# SOM_BOOT.net
KiCad netlist of a schematic drawn in Altium Designer
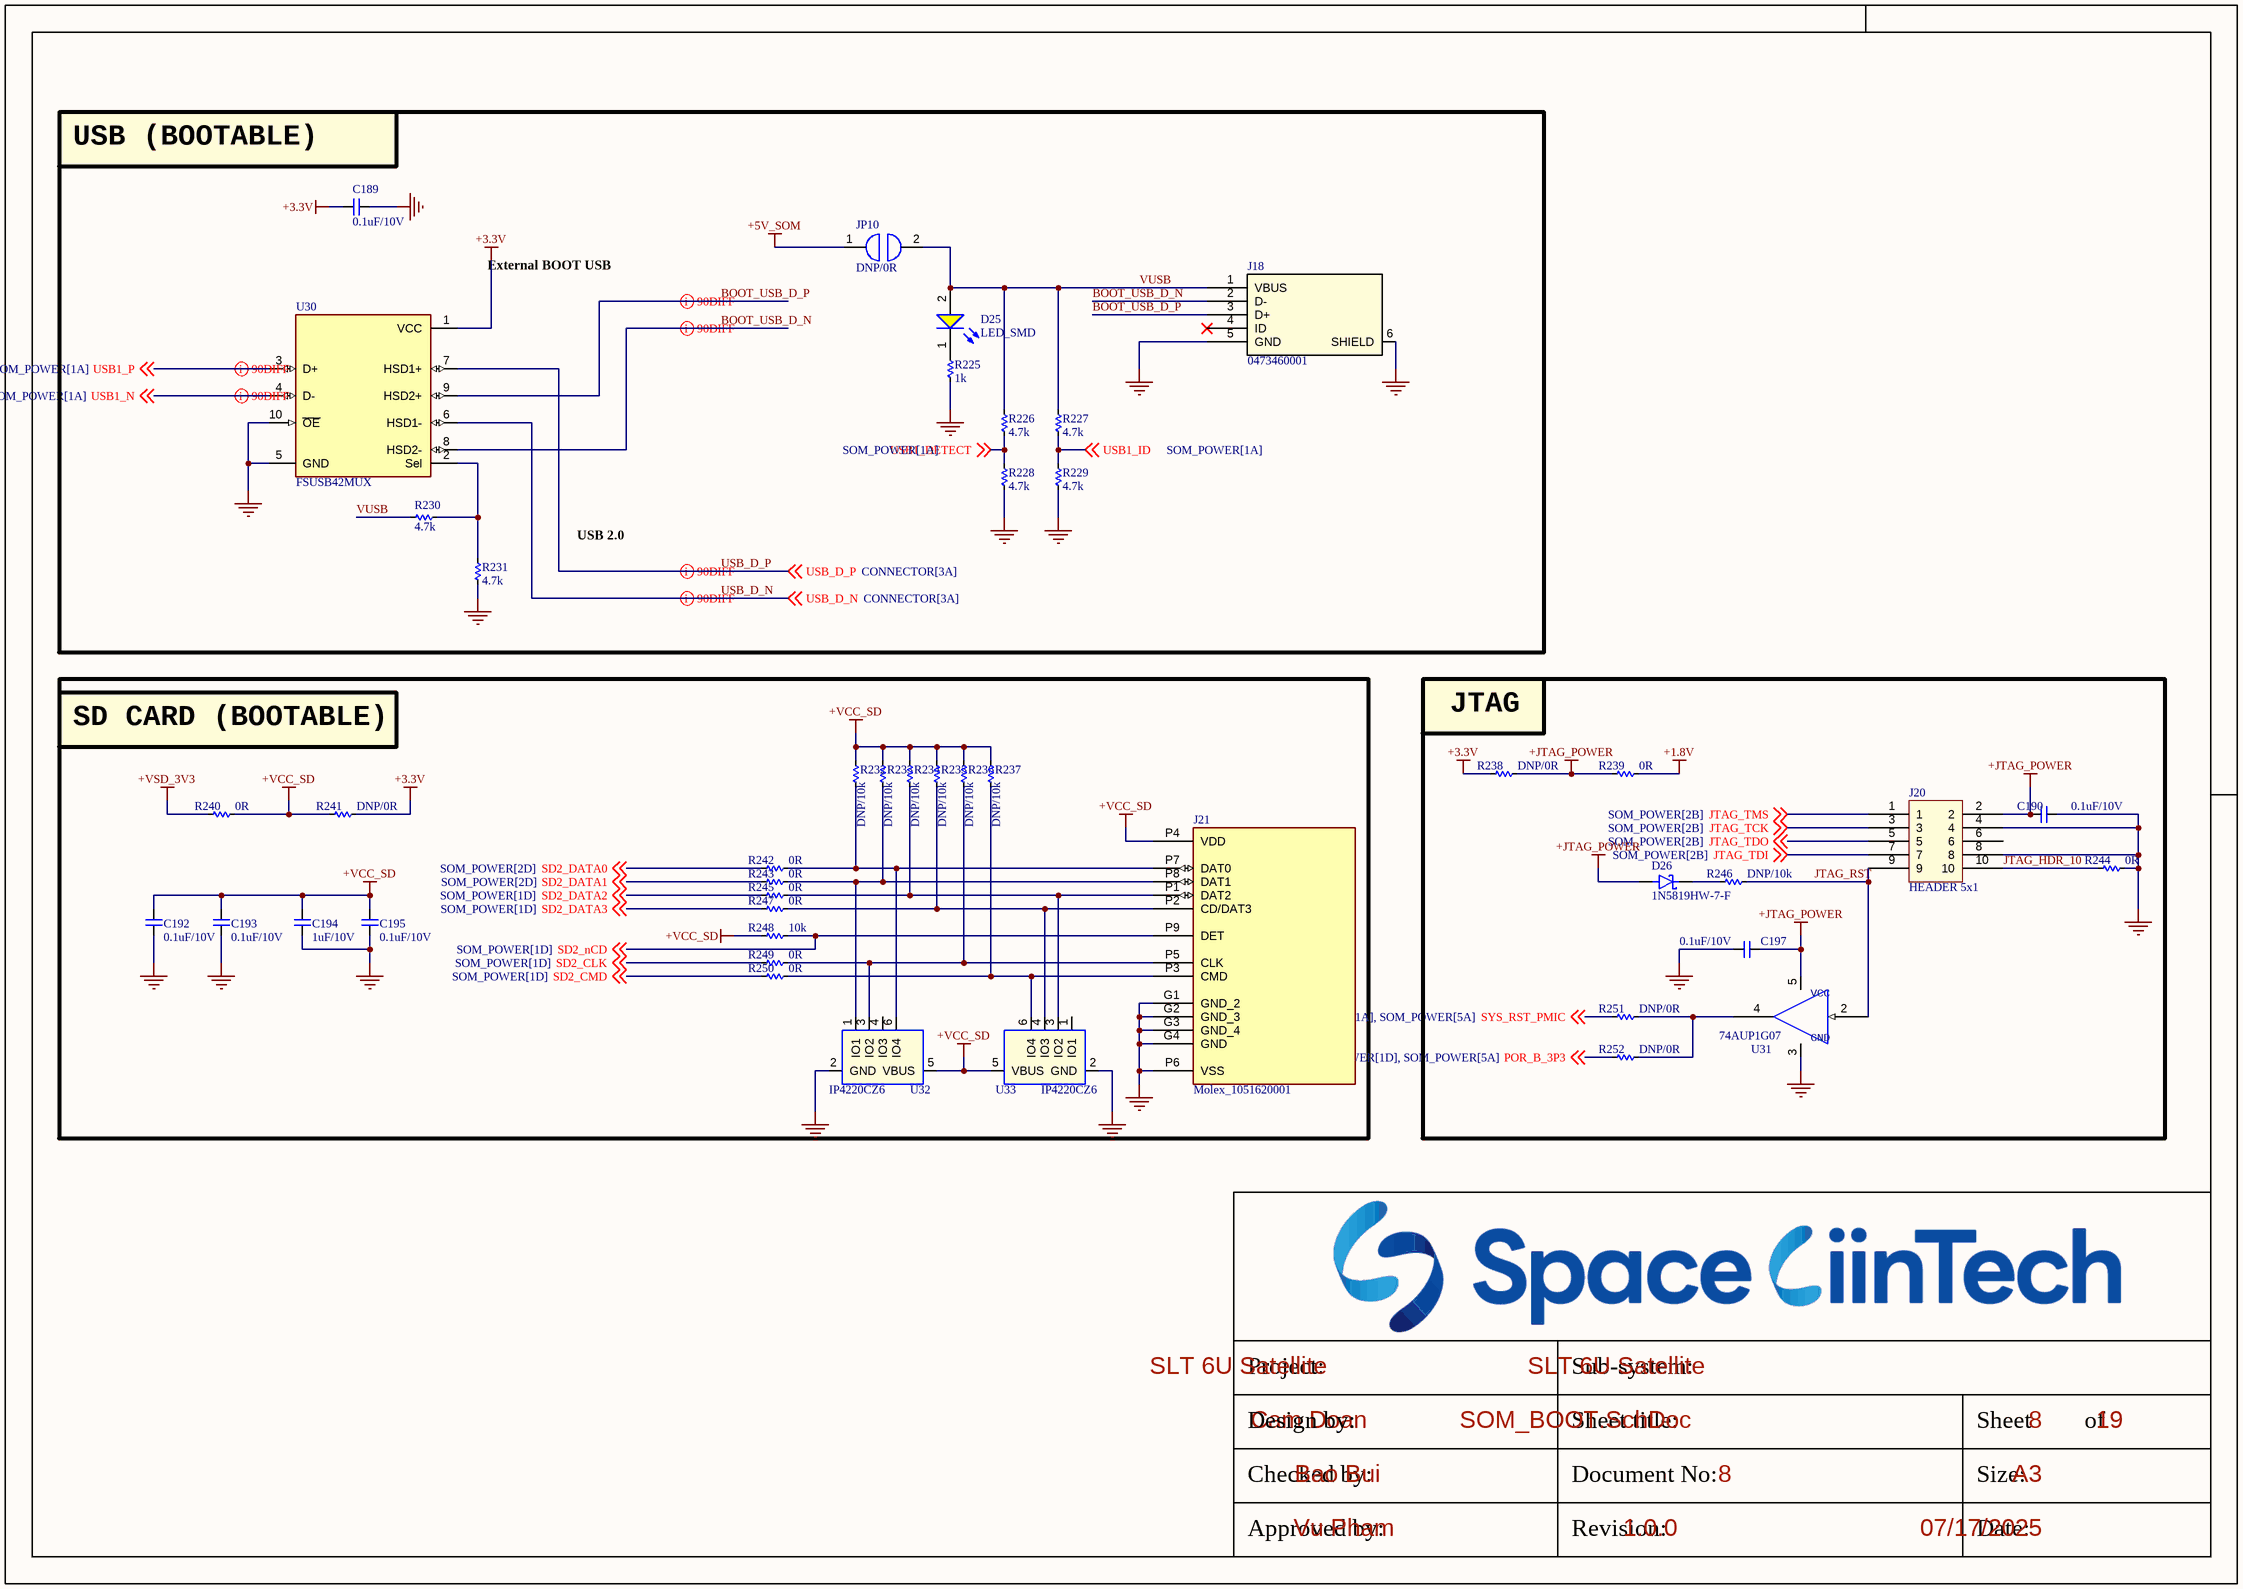
[diagram p0: SOM_BOOT.SchDoc]

(export (version "E")
  (design (tool "Eeschema 10.0.6"))
  (components
    (comp (ref "C189")
      (value "0.1uF/10V")
      (footprint "CAP_C_1005X60")
      (description "CAP CHIP")
      (libsource (lib "LABLIB") (part "_CAP_C_2"))
    )
    (comp (ref "C190")
      (value "0.1uF/10V")
      (footprint "CAP_C_1005X60")
      (description "CAP CHIP")
      (libsource (lib "LABLIB") (part "_CAP_C_2"))
    )
    (comp (ref "C192")
      (value "0.1uF/10V")
      (footprint "CAP_C_1005X60")
      (description "CAP CHIP")
      (libsource (lib "LABLIB") (part "_CAP_C_2"))
    )
    (comp (ref "C193")
      (value "0.1uF/10V")
      (footprint "CAP_C_1005X60")
      (description "CAP CHIP")
      (libsource (lib "LABLIB") (part "_CAP_C_2"))
    )
    (comp (ref "C194")
      (value "1uF/10V")
      (footprint "CAP_C_1005X60")
      (description "CAP CHIP")
      (libsource (lib "LABLIB") (part "_CAP_C_2"))
    )
    (comp (ref "C195")
      (value "0.1uF/10V")
      (footprint "CAP_C_1005X60")
      (description "CAP CHIP")
      (libsource (lib "LABLIB") (part "_CAP_C_2"))
    )
    (comp (ref "C197")
      (value "0.1uF/10V")
      (footprint "CAP_C_1005X60")
      (description "CAP CHIP")
      (libsource (lib "LABLIB") (part "_CAP_C_2"))
    )
    (comp (ref "D25") (value "LED_SMD") (footprint "LED_0603") (libsource (lib "LABLIB") (part "LED_SMD")))
    (comp (ref "D26")
      (value "1N5819HW-7-F")
      (footprint "SOD3717X145N")
      (description "DIODE SCHOTTKY 40V 1A SOD123")
      (libsource (lib "LABLIB") (part "DIODE SCHOTTKY"))
    )
    (comp (ref "J18")
      (value "0473460001")
      (footprint "47346-0001_MOL")
      (description "No Description Available")
      (libsource (lib "obc_ver2") (part "USB_micro"))
    )
    (comp (ref "J20")
      (value "HEADER 5x1")
      (footprint "CONN_54202-T0805ALF")
      (libsource (lib "LABLIB") (part "Header 5x2_Z"))
    )
    (comp (ref "J21")
      (value "Molex_1051620001")
      (footprint "Molex_1051620001")
      (description "9 (8 + 1) Position Card Connector Secure Digital - microSDâ„¢ Surface Mount, Right Angle Gold")
      (fields (field (name "MF") "Molex") (field (name "MP") "1051620001"))
      (libsource (lib "new_component") (part "Molex_1051620001"))
    )
    (comp (ref "JP10")
      (value "DNP/0R")
      (footprint "RES_C_1608X60")
      (libsource (lib "EXP_V1") (part "JUMPER"))
    )
    (comp (ref "R225")
      (value "1k")
      (footprint "RES_C_1005X40")
      (description "RES")
      (libsource (lib "LABLIB") (part "_RES_B_2"))
    )
    (comp (ref "R226")
      (value "4.7k")
      (footprint "RES_C_1005X40")
      (description "RES")
      (libsource (lib "LABLIB") (part "_RES_B_2"))
    )
    (comp (ref "R227")
      (value "4.7k")
      (footprint "RES_C_1005X40")
      (description "RES")
      (libsource (lib "LABLIB") (part "_RES_B_2"))
    )
    (comp (ref "R228")
      (value "4.7k")
      (footprint "RES_C_1005X40")
      (description "RES")
      (libsource (lib "LABLIB") (part "_RES_B_2"))
    )
    (comp (ref "R229")
      (value "4.7k")
      (footprint "RES_C_1005X40")
      (description "RES")
      (libsource (lib "LABLIB") (part "_RES_B_2"))
    )
    (comp (ref "R230")
      (value "4.7k")
      (footprint "RES_C_1005X40")
      (description "RES")
      (libsource (lib "LABLIB") (part "_RES_B_2"))
    )
    (comp (ref "R231")
      (value "4.7k")
      (footprint "RES_C_1005X40")
      (description "RES")
      (libsource (lib "LABLIB") (part "_RES_B_2"))
    )
    (comp (ref "R232")
      (value "DNP/10k")
      (footprint "RES_C_1005X40")
      (description "RES")
      (libsource (lib "LABLIB") (part "_RES_B_2"))
    )
    (comp (ref "R233")
      (value "DNP/10k")
      (footprint "RES_C_1005X40")
      (description "RES")
      (libsource (lib "LABLIB") (part "_RES_B_2"))
    )
    (comp (ref "R234")
      (value "DNP/10k")
      (footprint "RES_C_1005X40")
      (description "RES")
      (libsource (lib "LABLIB") (part "_RES_B_2"))
    )
    (comp (ref "R235")
      (value "DNP/10k")
      (footprint "RES_C_1005X40")
      (description "RES")
      (libsource (lib "LABLIB") (part "_RES_B_2"))
    )
    (comp (ref "R236")
      (value "DNP/10k")
      (footprint "RES_C_1005X40")
      (description "RES")
      (libsource (lib "LABLIB") (part "_RES_B_2"))
    )
    (comp (ref "R237")
      (value "DNP/10k")
      (footprint "RES_C_1005X40")
      (description "RES")
      (libsource (lib "LABLIB") (part "_RES_B_2"))
    )
    (comp (ref "R238")
      (value "DNP/0R")
      (footprint "RES_C_1005X40")
      (description "RES")
      (libsource (lib "LABLIB") (part "_RES_B_2"))
    )
    (comp (ref "R239")
      (value "0R")
      (footprint "RES_C_1005X40")
      (description "RES")
      (libsource (lib "LABLIB") (part "_RES_B_2"))
    )
    (comp (ref "R240")
      (value "0R")
      (footprint "RES_C_1005X40")
      (description "RES")
      (libsource (lib "LABLIB") (part "_RES_B_2"))
    )
    (comp (ref "R241")
      (value "DNP/0R")
      (footprint "RES_C_1005X40")
      (description "RES")
      (libsource (lib "LABLIB") (part "_RES_B_2"))
    )
    (comp (ref "R242")
      (value "0R")
      (footprint "RES_C_1005X40")
      (description "RES")
      (libsource (lib "LABLIB") (part "_RES_B_2"))
    )
    (comp (ref "R243")
      (value "0R")
      (footprint "RES_C_1005X40")
      (description "RES")
      (libsource (lib "LABLIB") (part "_RES_B_2"))
    )
    (comp (ref "R244")
      (value "0R")
      (footprint "RES_C_1005X40")
      (description "RES")
      (libsource (lib "LABLIB") (part "_RES_B_2"))
    )
    (comp (ref "R245")
      (value "0R")
      (footprint "RES_C_1005X40")
      (description "RES")
      (libsource (lib "LABLIB") (part "_RES_B_2"))
    )
    (comp (ref "R246")
      (value "DNP/10k")
      (footprint "RES_C_1005X40")
      (description "RES")
      (libsource (lib "LABLIB") (part "_RES_B_2"))
    )
    (comp (ref "R247")
      (value "0R")
      (footprint "RES_C_1005X40")
      (description "RES")
      (libsource (lib "LABLIB") (part "_RES_B_2"))
    )
    (comp (ref "R248")
      (value "10k")
      (footprint "RES_C_1005X40")
      (description "RES")
      (libsource (lib "LABLIB") (part "_RES_B_2"))
    )
    (comp (ref "R249")
      (value "0R")
      (footprint "RES_C_1005X40")
      (description "RES")
      (libsource (lib "LABLIB") (part "_RES_B_2"))
    )
    (comp (ref "R250")
      (value "0R")
      (footprint "RES_C_1005X40")
      (description "RES")
      (libsource (lib "LABLIB") (part "_RES_B_2"))
    )
    (comp (ref "R251")
      (value "DNP/0R")
      (footprint "RES_C_1005X40")
      (description "RES")
      (libsource (lib "LABLIB") (part "_RES_B_2"))
    )
    (comp (ref "R252")
      (value "DNP/0R")
      (footprint "RES_C_1005X40")
      (description "RES")
      (libsource (lib "LABLIB") (part "_RES_B_2"))
    )
    (comp (ref "U30")
      (value "FSUSB42MUX")
      (footprint "FP-846AP-MFG")
      (description "IC USB SWITCH DPDT 10MSOP")
      (fields (field (name "VOLTAGE") "4.3V"))
      (libsource (lib "Altium Content Vault") (part "e0bd5e1b4e0e4edc77f3356c64bf8f9"))
    )
    (comp (ref "U31")
      (value "74AUP1G07")
      (footprint "SOT-23-5_DIO")
      (libsource (lib "*") (part "74AUP1G07 , buffer ,LV"))
    )
    (comp (ref "U32")
      (value "IP4220CZ6")
      (footprint "SOT95P280X145-6N")
      (libsource (lib "*") (part "IP4220CZ6_0"))
    )
    (comp (ref "U33")
      (value "IP4220CZ6")
      (footprint "SOT95P280X145-6N")
      (libsource (lib "") (part "IP4220CZ6_0_1"))
    )
  )
  (nets
    (net (code "1") (name "+1.8V") (class "Default")
      (node (ref "R239") (pin "1") (pinfunction "1_1") (pintype "passive"))
    )
    (net (code "2") (name "+3.3V") (class "Default")
      (node (ref "C189") (pin "2") (pinfunction "2_2") (pintype "passive"))
      (node (ref "R238") (pin "2") (pinfunction "2_2") (pintype "passive"))
      (node (ref "R241") (pin "2") (pinfunction "2_2") (pintype "passive"))
      (node (ref "U30") (pin "1") (pinfunction "VCC_1") (pintype "power_in"))
    )
    (net (code "3") (name "+5V_SOM") (class "Default")
      (node (ref "JP10") (pin "1") (pinfunction "1_1") (pintype "passive"))
    )
    (net (code "4") (name "+JTAG_POWER") (class "Default")
      (node (ref "C190") (pin "2") (pinfunction "2_2") (pintype "passive"))
      (node (ref "C197") (pin "1") (pinfunction "1_1") (pintype "passive"))
      (node (ref "D26") (pin "2") (pinfunction "A_2") (pintype "passive"))
      (node (ref "J20") (pin "2") (pinfunction "2_2") (pintype "passive"))
      (node (ref "R238") (pin "1") (pinfunction "1_1") (pintype "passive"))
      (node (ref "R239") (pin "2") (pinfunction "2_2") (pintype "passive"))
      (node (ref "U31") (pin "5") (pinfunction "VCC_5") (pintype "power_in"))
    )
    (net (code "5") (name "+VCC_SD") (class "Default")
      (node (ref "C192") (pin "2") (pinfunction "2_2") (pintype "passive"))
      (node (ref "C193") (pin "2") (pinfunction "2_2") (pintype "passive"))
      (node (ref "C194") (pin "2") (pinfunction "2_2") (pintype "passive"))
      (node (ref "C195") (pin "2") (pinfunction "2_2") (pintype "passive"))
      (node (ref "J21") (pin "P4") (pinfunction "VDD_P4") (pintype "power_in"))
      (node (ref "R232") (pin "2") (pinfunction "2_2") (pintype "passive"))
      (node (ref "R233") (pin "2") (pinfunction "2_2") (pintype "passive"))
      (node (ref "R234") (pin "2") (pinfunction "2_2") (pintype "passive"))
      (node (ref "R235") (pin "2") (pinfunction "2_2") (pintype "passive"))
      (node (ref "R236") (pin "2") (pinfunction "2_2") (pintype "passive"))
      (node (ref "R237") (pin "2") (pinfunction "2_2") (pintype "passive"))
      (node (ref "R240") (pin "2") (pinfunction "2_2") (pintype "passive"))
      (node (ref "R241") (pin "1") (pinfunction "1_1") (pintype "passive"))
      (node (ref "R248") (pin "1") (pinfunction "1_1") (pintype "passive"))
      (node (ref "U32") (pin "5") (pinfunction "VBUS_5") (pintype "passive"))
      (node (ref "U33") (pin "5") (pinfunction "VBUS_5") (pintype "passive"))
    )
    (net (code "6") (name "+VSD_3V3") (class "Default")
      (node (ref "R240") (pin "1") (pinfunction "1_1") (pintype "passive"))
    )
    (net (code "7") (name "/BOOT_USB_D_N") (class "Default")
      (node (ref "J18") (pin "2") (pinfunction "D-_2") (pintype "passive"))
      (node (ref "U30") (pin "8") (pinfunction "HSD2-_8") (pintype "bidirectional"))
    )
    (net (code "8") (name "/BOOT_USB_D_P") (class "Default")
      (node (ref "J18") (pin "3") (pinfunction "D+_3") (pintype "passive"))
      (node (ref "U30") (pin "9") (pinfunction "HSD2+_9") (pintype "bidirectional"))
    )
    (net (code "9") (name "/JTAG_HDR_10") (class "Default")
      (node (ref "J20") (pin "10") (pinfunction "10_10") (pintype "passive"))
      (node (ref "R244") (pin "2") (pinfunction "2_2") (pintype "passive"))
    )
    (net (code "10") (name "/JTAG_RST") (class "Default")
      (node (ref "J20") (pin "9") (pinfunction "9_9") (pintype "passive"))
      (node (ref "R246") (pin "1") (pinfunction "1_1") (pintype "passive"))
      (node (ref "U31") (pin "2") (pinfunction "IN_2") (pintype "input"))
    )
    (net (code "11") (name "/VUSB") (class "Default")
      (node (ref "D25") (pin "2") (pinfunction "A_2") (pintype "passive"))
      (node (ref "J18") (pin "1") (pinfunction "VBUS_1") (pintype "passive"))
      (node (ref "JP10") (pin "2") (pinfunction "2_2") (pintype "passive"))
      (node (ref "R226") (pin "2") (pinfunction "2_2") (pintype "passive"))
      (node (ref "R227") (pin "2") (pinfunction "2_2") (pintype "passive"))
      (node (ref "R230") (pin "1") (pinfunction "1_1") (pintype "passive"))
    )
    (net (code "12") (name "GND") (class "Default")
      (node (ref "C189") (pin "1") (pinfunction "1_1") (pintype "passive"))
      (node (ref "C190") (pin "1") (pinfunction "1_1") (pintype "passive"))
      (node (ref "C192") (pin "1") (pinfunction "1_1") (pintype "passive"))
      (node (ref "C193") (pin "1") (pinfunction "1_1") (pintype "passive"))
      (node (ref "C194") (pin "1") (pinfunction "1_1") (pintype "passive"))
      (node (ref "C195") (pin "1") (pinfunction "1_1") (pintype "passive"))
      (node (ref "C197") (pin "2") (pinfunction "2_2") (pintype "passive"))
      (node (ref "J18") (pin "5") (pinfunction "GND_5") (pintype "power_in"))
      (node (ref "J18") (pin "6") (pinfunction "SHIELD_6") (pintype "passive"))
      (node (ref "J20") (pin "4") (pinfunction "4_4") (pintype "passive"))
      (node (ref "J20") (pin "8") (pinfunction "8_8") (pintype "passive"))
      (node (ref "J21") (pin "G1") (pinfunction "GND_2_G1") (pintype "passive"))
      (node (ref "J21") (pin "G2") (pinfunction "GND_3_G2") (pintype "passive"))
      (node (ref "J21") (pin "G3") (pinfunction "GND_4_G3") (pintype "passive"))
      (node (ref "J21") (pin "G4") (pinfunction "GND_G4") (pintype "passive"))
      (node (ref "J21") (pin "P6") (pinfunction "VSS_P6") (pintype "passive"))
      (node (ref "R225") (pin "1") (pinfunction "1_1") (pintype "passive"))
      (node (ref "R228") (pin "1") (pinfunction "1_1") (pintype "passive"))
      (node (ref "R229") (pin "1") (pinfunction "1_1") (pintype "passive"))
      (node (ref "R231") (pin "1") (pinfunction "1_1") (pintype "passive"))
      (node (ref "R244") (pin "1") (pinfunction "1_1") (pintype "passive"))
      (node (ref "U30") (pin "10") (pinfunction "~{OE}_10") (pintype "input"))
      (node (ref "U30") (pin "5") (pinfunction "GND_5") (pintype "power_in"))
      (node (ref "U31") (pin "3") (pinfunction "GND_3") (pintype "power_in"))
      (node (ref "U32") (pin "2") (pinfunction "GND_2") (pintype "passive"))
      (node (ref "U33") (pin "2") (pinfunction "GND_2") (pintype "passive"))
    )
    (net (code "13") (name "JTAG_TCK") (class "Default")
      (node (ref "J20") (pin "3") (pinfunction "3_3") (pintype "passive"))
    )
    (net (code "14") (name "JTAG_TDI") (class "Default")
      (node (ref "J20") (pin "7") (pinfunction "7_7") (pintype "passive"))
    )
    (net (code "15") (name "JTAG_TDO") (class "Default")
      (node (ref "J20") (pin "5") (pinfunction "5_5") (pintype "passive"))
    )
    (net (code "16") (name "JTAG_TMS") (class "Default")
      (node (ref "J20") (pin "1") (pinfunction "1_1") (pintype "passive"))
    )
    (net (code "17") (name "Net-(D25-K)") (class "Default")
      (node (ref "D25") (pin "1") (pinfunction "K_1") (pintype "passive"))
      (node (ref "R225") (pin "2") (pinfunction "2_2") (pintype "passive"))
    )
    (net (code "18") (name "Net-(D26-K)") (class "Default")
      (node (ref "D26") (pin "1") (pinfunction "K_1") (pintype "passive"))
      (node (ref "R246") (pin "2") (pinfunction "2_2") (pintype "passive"))
    )
    (net (code "19") (name "Net-(J21-CD{slash}DAT3)") (class "Default")
      (node (ref "J21") (pin "P2") (pinfunction "CD/DAT3_P2") (pintype "passive"))
      (node (ref "R235") (pin "1") (pinfunction "1_1") (pintype "passive"))
      (node (ref "R247") (pin "2") (pinfunction "2_2") (pintype "passive"))
      (node (ref "U33") (pin "4") (pinfunction "IO3_4") (pintype "passive"))
    )
    (net (code "20") (name "Net-(J21-CLK)") (class "Default")
      (node (ref "J21") (pin "P5") (pinfunction "CLK_P5") (pintype "passive"))
      (node (ref "R236") (pin "1") (pinfunction "1_1") (pintype "passive"))
      (node (ref "R249") (pin "2") (pinfunction "2_2") (pintype "passive"))
      (node (ref "U32") (pin "3") (pinfunction "IO2_3") (pintype "passive"))
    )
    (net (code "21") (name "Net-(J21-CMD)") (class "Default")
      (node (ref "J21") (pin "P3") (pinfunction "CMD_P3") (pintype "passive"))
      (node (ref "R237") (pin "1") (pinfunction "1_1") (pintype "passive"))
      (node (ref "R250") (pin "2") (pinfunction "2_2") (pintype "passive"))
      (node (ref "U33") (pin "6") (pinfunction "IO4_6") (pintype "passive"))
    )
    (net (code "22") (name "Net-(J21-DAT0)") (class "Default")
      (node (ref "J21") (pin "P7") (pinfunction "DAT0_P7") (pintype "bidirectional"))
      (node (ref "R232") (pin "1") (pinfunction "1_1") (pintype "passive"))
      (node (ref "R242") (pin "2") (pinfunction "2_2") (pintype "passive"))
      (node (ref "U32") (pin "6") (pinfunction "IO4_6") (pintype "passive"))
    )
    (net (code "23") (name "Net-(J21-DAT1)") (class "Default")
      (node (ref "J21") (pin "P8") (pinfunction "DAT1_P8") (pintype "bidirectional"))
      (node (ref "R233") (pin "1") (pinfunction "1_1") (pintype "passive"))
      (node (ref "R243") (pin "2") (pinfunction "2_2") (pintype "passive"))
      (node (ref "U32") (pin "1") (pinfunction "IO1_1") (pintype "passive"))
    )
    (net (code "24") (name "Net-(J21-DAT2)") (class "Default")
      (node (ref "J21") (pin "P1") (pinfunction "DAT2_P1") (pintype "bidirectional"))
      (node (ref "R234") (pin "1") (pinfunction "1_1") (pintype "passive"))
      (node (ref "R245") (pin "2") (pinfunction "2_2") (pintype "passive"))
      (node (ref "U33") (pin "3") (pinfunction "IO2_3") (pintype "passive"))
    )
    (net (code "25") (name "Net-(U30-Sel)") (class "Default")
      (node (ref "R230") (pin "2") (pinfunction "2_2") (pintype "passive"))
      (node (ref "R231") (pin "2") (pinfunction "2_2") (pintype "passive"))
      (node (ref "U30") (pin "2") (pinfunction "Sel_2") (pintype "passive"))
    )
    (net (code "26") (name "Net-(U31-OUT)") (class "Default")
      (node (ref "R251") (pin "1") (pinfunction "1_1") (pintype "passive"))
      (node (ref "R252") (pin "1") (pinfunction "1_1") (pintype "passive"))
      (node (ref "U31") (pin "4") (pinfunction "OUT_4") (pintype "open_collector"))
    )
    (net (code "27") (name "POR_B_3P3") (class "Default")
      (node (ref "R252") (pin "2") (pinfunction "2_2") (pintype "passive"))
    )
    (net (code "28") (name "SD2_CLK") (class "Default")
      (node (ref "R249") (pin "1") (pinfunction "1_1") (pintype "passive"))
    )
    (net (code "29") (name "SD2_CMD") (class "Default")
      (node (ref "R250") (pin "1") (pinfunction "1_1") (pintype "passive"))
    )
    (net (code "30") (name "SD2_DATA0") (class "Default")
      (node (ref "R242") (pin "1") (pinfunction "1_1") (pintype "passive"))
    )
    (net (code "31") (name "SD2_DATA1") (class "Default")
      (node (ref "R243") (pin "1") (pinfunction "1_1") (pintype "passive"))
    )
    (net (code "32") (name "SD2_DATA2") (class "Default")
      (node (ref "R245") (pin "1") (pinfunction "1_1") (pintype "passive"))
    )
    (net (code "33") (name "SD2_DATA3") (class "Default")
      (node (ref "R247") (pin "1") (pinfunction "1_1") (pintype "passive"))
    )
    (net (code "34") (name "SD2_nCD") (class "Default")
      (node (ref "J21") (pin "P9") (pinfunction "DET_P9") (pintype "passive"))
      (node (ref "R248") (pin "2") (pinfunction "2_2") (pintype "passive"))
    )
    (net (code "35") (name "SYS_RST_PMIC") (class "Default")
      (node (ref "R251") (pin "2") (pinfunction "2_2") (pintype "passive"))
    )
    (net (code "36") (name "USB1_DETECT") (class "Default")
      (node (ref "R226") (pin "1") (pinfunction "1_1") (pintype "passive"))
      (node (ref "R228") (pin "2") (pinfunction "2_2") (pintype "passive"))
    )
    (net (code "37") (name "USB1_ID") (class "Default")
      (node (ref "R227") (pin "1") (pinfunction "1_1") (pintype "passive"))
      (node (ref "R229") (pin "2") (pinfunction "2_2") (pintype "passive"))
    )
    (net (code "38") (name "USB1_N") (class "Default")
      (node (ref "U30") (pin "4") (pinfunction "D-_4") (pintype "bidirectional"))
    )
    (net (code "39") (name "USB1_P") (class "Default")
      (node (ref "U30") (pin "3") (pinfunction "D+_3") (pintype "bidirectional"))
    )
    (net (code "40") (name "USB_D_N") (class "Default")
      (node (ref "U30") (pin "6") (pinfunction "HSD1-_6") (pintype "bidirectional"))
    )
    (net (code "41") (name "USB_D_P") (class "Default")
      (node (ref "U30") (pin "7") (pinfunction "HSD1+_7") (pintype "bidirectional"))
    )
    (net (code "42") (name "unconnected-(J18-ID-Pad4)") (class "Default")
      (node (ref "J18") (pin "4") (pinfunction "ID_4") (pintype "passive+no_connect"))
    )
    (net (code "43") (name "unconnected-(J20-Pad6)") (class "Default")
      (node (ref "J20") (pin "6") (pinfunction "6_6") (pintype "passive"))
    )
    (net (code "44") (name "unconnected-(U32-IO3-Pad4)") (class "Default")
      (node (ref "U32") (pin "4") (pinfunction "IO3_4") (pintype "passive"))
    )
    (net (code "45") (name "unconnected-(U33-IO1-Pad1)") (class "Default")
      (node (ref "U33") (pin "1") (pinfunction "IO1_1") (pintype "passive"))
    )
  )
)
